# Power_Board_Testing_Interface_Board_manu.net
KiCad netlist of a schematic drawn in EAGLE
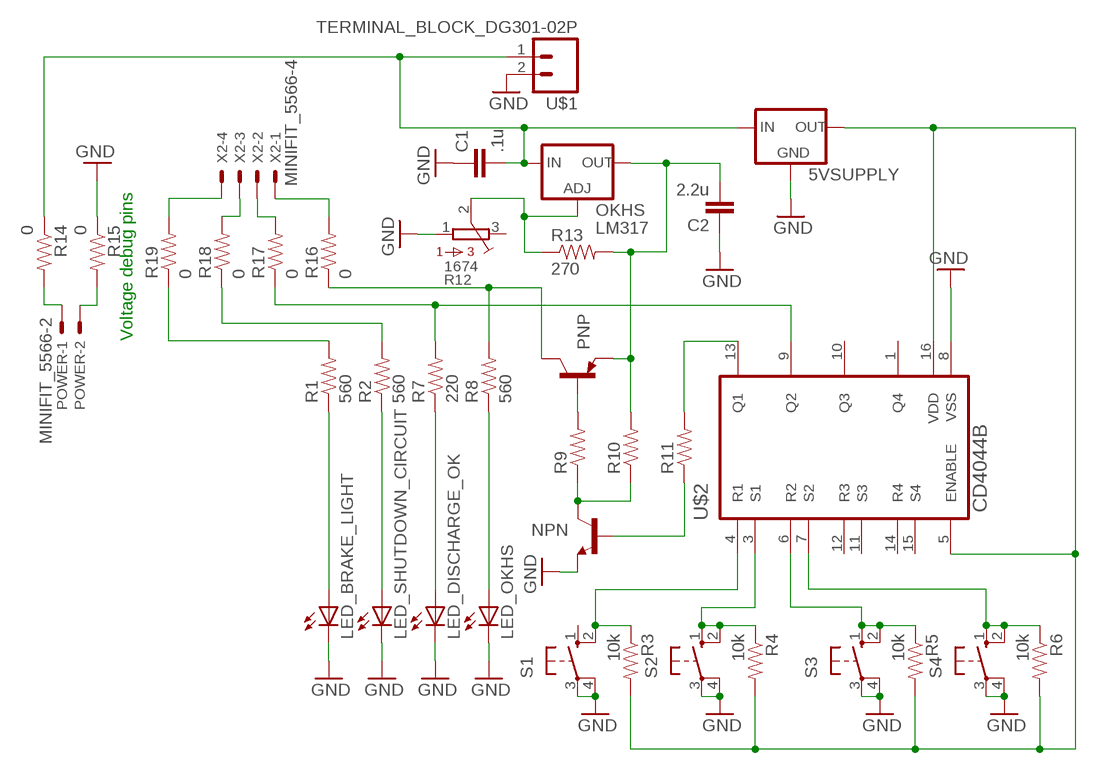
[diagram p0: schematic, sheet 1]

(export (version "E")
  (design (tool "Eeschema 10.0.6"))
  (components
    (comp (ref "5VSUPPLY")
      (value "5V_REGULATOR_L7805SWITCHING")
      (footprint "eagle-import:TO-220")
      (libsource (lib "eagle-import") (part "5V_REGULATOR_L7805SWITCHING"))
    )
    (comp (ref "C1")
      (value ".1u")
      (footprint "eagle-import:CAP-PTH-SMALLEZ")
      (libsource (lib "eagle-import") (part "CAPEZ"))
    )
    (comp (ref "C2")
      (value "2.2u")
      (footprint "eagle-import:CAP-PTH-5MM")
      (libsource (lib "eagle-import") (part "CAPPTH1"))
    )
    (comp (ref "LED_BRAKE_LIGHT")
      (value "LED-5MM")
      (footprint "eagle-import:LED-5MM")
      (libsource (lib "eagle-import") (part "LED-5MM"))
    )
    (comp (ref "LED_DISCHARGE_OK")
      (value "LED-5MM")
      (footprint "eagle-import:LED-5MM")
      (libsource (lib "eagle-import") (part "LED-5MM"))
    )
    (comp (ref "LED_OKHS")
      (value "LED-5MM")
      (footprint "eagle-import:LED-5MM")
      (libsource (lib "eagle-import") (part "LED-5MM"))
    )
    (comp (ref "LED_SHUTDOWN_CIRCUIT")
      (value "LED-5MM")
      (footprint "eagle-import:LED-5MM")
      (libsource (lib "eagle-import") (part "LED-5MM"))
    )
    (comp (ref "NPN")
      (value "BJT_NPNTIP120")
      (footprint "eagle-import:TO-220")
      (libsource (lib "eagle-import") (part "BJT_NPNTIP120"))
    )
    (comp (ref "OKHS")
      (value "LM317")
      (footprint "eagle-import:TO-220")
      (libsource (lib "eagle-import") (part "LM317"))
    )
    (comp (ref "PNP")
      (value "BJT_PNP")
      (footprint "eagle-import:TO-220")
      (libsource (lib "eagle-import") (part "BJT_PNP"))
    )
    (comp (ref "POWER")
      (value "MINIFIT_5566-2")
      (footprint "eagle-import:MINIFIT_5566-2")
      (libsource (lib "eagle-import") (part "MINIFIT_5566-2"))
    )
    (comp (ref "R1")
      (value "560")
      (footprint "eagle-import:AXIAL-0.3EZ")
      (libsource (lib "eagle-import") (part "RESISTOREZ"))
    )
    (comp (ref "R2")
      (value "560")
      (footprint "eagle-import:AXIAL-0.3EZ")
      (libsource (lib "eagle-import") (part "RESISTOREZ"))
    )
    (comp (ref "R3")
      (value "10k")
      (footprint "eagle-import:AXIAL-0.3EZ")
      (libsource (lib "eagle-import") (part "RESISTOREZ"))
    )
    (comp (ref "R4")
      (value "10k")
      (footprint "eagle-import:AXIAL-0.3EZ")
      (libsource (lib "eagle-import") (part "RESISTOREZ"))
    )
    (comp (ref "R5")
      (value "10k")
      (footprint "eagle-import:AXIAL-0.3EZ")
      (libsource (lib "eagle-import") (part "RESISTOREZ"))
    )
    (comp (ref "R6")
      (value "10k")
      (footprint "eagle-import:AXIAL-0.3EZ")
      (libsource (lib "eagle-import") (part "RESISTOREZ"))
    )
    (comp (ref "R7")
      (value "220")
      (footprint "eagle-import:AXIAL-0.3EZ")
      (libsource (lib "eagle-import") (part "RESISTOREZ"))
    )
    (comp (ref "R8")
      (value "560")
      (footprint "eagle-import:AXIAL-0.3EZ")
      (libsource (lib "eagle-import") (part "RESISTOREZ"))
    )
    (comp (ref "R9")
      (value "RESISTOREZ")
      (footprint "eagle-import:AXIAL-0.3EZ")
      (libsource (lib "eagle-import") (part "RESISTOREZ"))
    )
    (comp (ref "R10")
      (value "RESISTOREZ")
      (footprint "eagle-import:AXIAL-0.3EZ")
      (libsource (lib "eagle-import") (part "RESISTOREZ"))
    )
    (comp (ref "R11")
      (value "RESISTOREZ")
      (footprint "eagle-import:AXIAL-0.3EZ")
      (libsource (lib "eagle-import") (part "RESISTOREZ"))
    )
    (comp (ref "R12")
      (value "1674")
      (footprint "eagle-import:TRIMPOT_3296")
      (libsource (lib "eagle-import") (part "TRIMPOT_3296C"))
    )
    (comp (ref "R13")
      (value "270")
      (footprint "eagle-import:AXIAL-0.3EZ")
      (libsource (lib "eagle-import") (part "RESISTOREZ"))
    )
    (comp (ref "R14")
      (value "0")
      (footprint "eagle-import:AXIAL-0.3EZ")
      (libsource (lib "eagle-import") (part "RESISTOREZ"))
    )
    (comp (ref "R15")
      (value "0")
      (footprint "eagle-import:AXIAL-0.3EZ")
      (libsource (lib "eagle-import") (part "RESISTOREZ"))
    )
    (comp (ref "R16")
      (value "0")
      (footprint "eagle-import:AXIAL-0.3EZ")
      (libsource (lib "eagle-import") (part "RESISTOREZ"))
    )
    (comp (ref "R17")
      (value "0")
      (footprint "eagle-import:AXIAL-0.3EZ")
      (libsource (lib "eagle-import") (part "RESISTOREZ"))
    )
    (comp (ref "R18")
      (value "0")
      (footprint "eagle-import:AXIAL-0.3EZ")
      (libsource (lib "eagle-import") (part "RESISTOREZ"))
    )
    (comp (ref "R19")
      (value "0")
      (footprint "eagle-import:AXIAL-0.3EZ")
      (libsource (lib "eagle-import") (part "RESISTOREZ"))
    )
    (comp (ref "S1")
      (value "BTN_10-XX")
      (footprint "eagle-import:B3F-10XX")
      (fields (field (name "MPN") "B3F-1000"))
      (libsource (lib "eagle-import") (part "BTN_10-XX"))
    )
    (comp (ref "S2")
      (value "BTN_10-XX")
      (footprint "eagle-import:B3F-10XX")
      (fields (field (name "MPN") "B3F-1000"))
      (libsource (lib "eagle-import") (part "BTN_10-XX"))
    )
    (comp (ref "S3")
      (value "BTN_10-XX")
      (footprint "eagle-import:B3F-10XX")
      (fields (field (name "MPN") "B3F-1000"))
      (libsource (lib "eagle-import") (part "BTN_10-XX"))
    )
    (comp (ref "S4")
      (value "BTN_10-XX")
      (footprint "eagle-import:B3F-10XX")
      (fields (field (name "MPN") "B3F-1000"))
      (libsource (lib "eagle-import") (part "BTN_10-XX"))
    )
    (comp (ref "U$1")
      (value "TERMINAL_BLOCK_DG301-02P")
      (footprint "eagle-import:DG301-02P")
      (libsource (lib "eagle-import") (part "TERMINAL_BLOCK_DG301-02P"))
    )
    (comp (ref "U$2")
      (value "CD4044B")
      (footprint "eagle-import:DIL16")
      (libsource (lib "eagle-import") (part "CD4044B"))
    )
    (comp (ref "X2")
      (value "MINIFIT_5566-4")
      (footprint "eagle-import:MINIFIT_5566-4")
      (libsource (lib "eagle-import") (part "MINIFIT_5566-4"))
    )
  )
  (nets
    (net (code "1") (name "GND") (class "Default")
      (node (ref "5VSUPPLY") (pin "2") (pinfunction "GND_2") (pintype "input"))
      (node (ref "C1") (pin "1") (pinfunction "1_1") (pintype "passive"))
      (node (ref "C2") (pin "1") (pinfunction "1_1") (pintype "passive"))
      (node (ref "LED_BRAKE_LIGHT") (pin "K") (pinfunction "C_K") (pintype "passive"))
      (node (ref "LED_DISCHARGE_OK") (pin "K") (pinfunction "C_K") (pintype "passive"))
      (node (ref "LED_OKHS") (pin "K") (pinfunction "C_K") (pintype "passive"))
      (node (ref "LED_SHUTDOWN_CIRCUIT") (pin "K") (pinfunction "C_K") (pintype "passive"))
      (node (ref "NPN") (pin "3") (pinfunction "EMITTER_3") (pintype "passive"))
      (node (ref "R12") (pin "1") (pinfunction "1_1") (pintype "passive"))
      (node (ref "R15") (pin "P$1") (pinfunction "1_P$1") (pintype "passive"))
      (node (ref "S1") (pin "3") (pinfunction "P_3") (pintype "passive"))
      (node (ref "S1") (pin "4") (pinfunction "P1_4") (pintype "passive"))
      (node (ref "S2") (pin "3") (pinfunction "P_3") (pintype "passive"))
      (node (ref "S2") (pin "4") (pinfunction "P1_4") (pintype "passive"))
      (node (ref "S3") (pin "3") (pinfunction "P_3") (pintype "passive"))
      (node (ref "S3") (pin "4") (pinfunction "P1_4") (pintype "passive"))
      (node (ref "S4") (pin "3") (pinfunction "P_3") (pintype "passive"))
      (node (ref "S4") (pin "4") (pinfunction "P1_4") (pintype "passive"))
      (node (ref "U$1") (pin "2") (pinfunction "2_2") (pintype "passive"))
      (node (ref "U$2") (pin "8") (pinfunction "VSS_8") (pintype "output"))
    )
    (net (code "2") (name "Net-(5VSUPPLY-IN)") (class "Default")
      (node (ref "5VSUPPLY") (pin "1") (pinfunction "IN_1") (pintype "input"))
      (node (ref "C1") (pin "2") (pinfunction "2_2") (pintype "passive"))
      (node (ref "OKHS") (pin "3") (pinfunction "IN_3") (pintype "input"))
      (node (ref "R14") (pin "P$1") (pinfunction "1_P$1") (pintype "passive"))
      (node (ref "U$1") (pin "1") (pinfunction "1_1") (pintype "passive"))
    )
    (net (code "3") (name "Net-(5VSUPPLY-OUT)") (class "Default")
      (node (ref "5VSUPPLY") (pin "3") (pinfunction "OUT_3") (pintype "output"))
      (node (ref "R3") (pin "P$2") (pinfunction "2_P$2") (pintype "passive"))
      (node (ref "R4") (pin "P$2") (pinfunction "2_P$2") (pintype "passive"))
      (node (ref "R5") (pin "P$2") (pinfunction "2_P$2") (pintype "passive"))
      (node (ref "R6") (pin "P$2") (pinfunction "2_P$2") (pintype "passive"))
      (node (ref "U$2") (pin "16") (pinfunction "VDD_16") (pintype "input"))
      (node (ref "U$2") (pin "5") (pinfunction "ENABLE_5") (pintype "input"))
    )
    (net (code "4") (name "Net-(NPN-BASE)") (class "Default")
      (node (ref "NPN") (pin "1") (pinfunction "BASE_1") (pintype "passive"))
      (node (ref "R11") (pin "P$1") (pinfunction "1_P$1") (pintype "passive"))
    )
    (net (code "5") (name "Net-(NPN-COLLECTOR)") (class "Default")
      (node (ref "NPN") (pin "2") (pinfunction "COLLECTOR_2") (pintype "passive"))
      (node (ref "R10") (pin "P$1") (pinfunction "1_P$1") (pintype "passive"))
      (node (ref "R9") (pin "P$1") (pinfunction "1_P$1") (pintype "passive"))
    )
    (net (code "6") (name "Net-(OKHS-ADJ)") (class "Default")
      (node (ref "OKHS") (pin "1") (pinfunction "ADJ_1") (pintype "input"))
      (node (ref "R12") (pin "2") (pinfunction "2_2") (pintype "passive"))
      (node (ref "R13") (pin "P$1") (pinfunction "1_P$1") (pintype "passive"))
    )
    (net (code "7") (name "Net-(OKHS-OUT)") (class "Default")
      (node (ref "C2") (pin "2") (pinfunction "2_2") (pintype "passive"))
      (node (ref "OKHS") (pin "2") (pinfunction "OUT_2") (pintype "output"))
      (node (ref "PNP") (pin "3") (pinfunction "E_3") (pintype "passive"))
      (node (ref "R10") (pin "P$2") (pinfunction "2_P$2") (pintype "passive"))
      (node (ref "R13") (pin "P$2") (pinfunction "2_P$2") (pintype "passive"))
    )
    (net (code "8") (name "Net-(PNP-B)") (class "Default")
      (node (ref "PNP") (pin "1") (pinfunction "B_1") (pintype "passive"))
      (node (ref "R9") (pin "P$2") (pinfunction "2_P$2") (pintype "passive"))
    )
    (net (code "9") (name "Net-(PNP-C)") (class "Default")
      (node (ref "PNP") (pin "2") (pinfunction "C_2") (pintype "passive"))
      (node (ref "R16") (pin "P$1") (pinfunction "1_P$1") (pintype "passive"))
      (node (ref "R8") (pin "P$2") (pinfunction "2_P$2") (pintype "passive"))
    )
    (net (code "10") (name "Net-(POWERA-S)") (class "Default")
      (node (ref "POWER") (pin "1") (pinfunction "S_1") (pintype "passive"))
      (node (ref "R14") (pin "P$2") (pinfunction "2_P$2") (pintype "passive"))
    )
    (net (code "11") (name "Net-(POWERB-S)") (class "Default")
      (node (ref "POWER") (pin "2") (pinfunction "S_2") (pintype "passive"))
      (node (ref "R15") (pin "P$2") (pinfunction "2_P$2") (pintype "passive"))
    )
    (net (code "12") (name "Net-(R1-1)") (class "Default")
      (node (ref "LED_BRAKE_LIGHT") (pin "A") (pinfunction "A_A") (pintype "passive"))
      (node (ref "R1") (pin "P$1") (pinfunction "1_P$1") (pintype "passive"))
    )
    (net (code "13") (name "Net-(R1-2)") (class "Default")
      (node (ref "R1") (pin "P$2") (pinfunction "2_P$2") (pintype "passive"))
      (node (ref "R19") (pin "P$1") (pinfunction "1_P$1") (pintype "passive"))
    )
    (net (code "14") (name "Net-(R2-1)") (class "Default")
      (node (ref "LED_SHUTDOWN_CIRCUIT") (pin "A") (pinfunction "A_A") (pintype "passive"))
      (node (ref "R2") (pin "P$1") (pinfunction "1_P$1") (pintype "passive"))
    )
    (net (code "15") (name "Net-(R3-1)") (class "Default")
      (node (ref "R3") (pin "P$1") (pinfunction "1_P$1") (pintype "passive"))
      (node (ref "S1") (pin "2") (pinfunction "S1_2") (pintype "passive"))
      (node (ref "U$2") (pin "4") (pinfunction "R1_4") (pintype "input"))
    )
    (net (code "16") (name "Net-(R4-1)") (class "Default")
      (node (ref "R4") (pin "P$1") (pinfunction "1_P$1") (pintype "passive"))
      (node (ref "S2") (pin "1") (pinfunction "S_1") (pintype "passive"))
      (node (ref "S2") (pin "2") (pinfunction "S1_2") (pintype "passive"))
      (node (ref "U$2") (pin "3") (pinfunction "S1_3") (pintype "input"))
    )
    (net (code "17") (name "Net-(R5-1)") (class "Default")
      (node (ref "R5") (pin "P$1") (pinfunction "1_P$1") (pintype "passive"))
      (node (ref "S3") (pin "1") (pinfunction "S_1") (pintype "passive"))
      (node (ref "S3") (pin "2") (pinfunction "S1_2") (pintype "passive"))
      (node (ref "U$2") (pin "6") (pinfunction "R2_6") (pintype "input"))
    )
    (net (code "18") (name "Net-(R6-1)") (class "Default")
      (node (ref "R6") (pin "P$1") (pinfunction "1_P$1") (pintype "passive"))
      (node (ref "S4") (pin "1") (pinfunction "S_1") (pintype "passive"))
      (node (ref "S4") (pin "2") (pinfunction "S1_2") (pintype "passive"))
      (node (ref "U$2") (pin "7") (pinfunction "S2_7") (pintype "input"))
    )
    (net (code "19") (name "Net-(R7-1)") (class "Default")
      (node (ref "LED_DISCHARGE_OK") (pin "A") (pinfunction "A_A") (pintype "passive"))
      (node (ref "R7") (pin "P$1") (pinfunction "1_P$1") (pintype "passive"))
    )
    (net (code "20") (name "Net-(R8-1)") (class "Default")
      (node (ref "LED_OKHS") (pin "A") (pinfunction "A_A") (pintype "passive"))
      (node (ref "R8") (pin "P$1") (pinfunction "1_P$1") (pintype "passive"))
    )
    (net (code "21") (name "Net-(R11-2)") (class "Default")
      (node (ref "R11") (pin "P$2") (pinfunction "2_P$2") (pintype "passive"))
      (node (ref "U$2") (pin "13") (pinfunction "Q1_13") (pintype "output"))
    )
    (net (code "22") (name "Net-(R16-2)") (class "Default")
      (node (ref "R16") (pin "P$2") (pinfunction "2_P$2") (pintype "passive"))
      (node (ref "X2") (pin "1") (pinfunction "S_1") (pintype "passive"))
    )
    (net (code "23") (name "Net-(R17-1)") (class "Default")
      (node (ref "R17") (pin "P$1") (pinfunction "1_P$1") (pintype "passive"))
      (node (ref "R7") (pin "P$2") (pinfunction "2_P$2") (pintype "passive"))
      (node (ref "U$2") (pin "9") (pinfunction "Q2_9") (pintype "output"))
    )
    (net (code "24") (name "Net-(R17-2)") (class "Default")
      (node (ref "R17") (pin "P$2") (pinfunction "2_P$2") (pintype "passive"))
      (node (ref "X2") (pin "2") (pinfunction "S_2") (pintype "passive"))
    )
    (net (code "25") (name "Net-(R18-1)") (class "Default")
      (node (ref "R18") (pin "P$1") (pinfunction "1_P$1") (pintype "passive"))
      (node (ref "R2") (pin "P$2") (pinfunction "2_P$2") (pintype "passive"))
    )
    (net (code "26") (name "Net-(R18-2)") (class "Default")
      (node (ref "R18") (pin "P$2") (pinfunction "2_P$2") (pintype "passive"))
      (node (ref "X2") (pin "3") (pinfunction "S_3") (pintype "passive"))
    )
    (net (code "27") (name "Net-(R19-2)") (class "Default")
      (node (ref "R19") (pin "P$2") (pinfunction "2_P$2") (pintype "passive"))
      (node (ref "X2") (pin "4") (pinfunction "S_4") (pintype "passive"))
    )
    (net (code "28") (name "unconnected-(R12-Pad3)") (class "Default")
      (node (ref "R12") (pin "3") (pinfunction "3_3") (pintype "passive"))
    )
    (net (code "29") (name "unconnected-(S1-S-Pad1)") (class "Default")
      (node (ref "S1") (pin "1") (pinfunction "S_1") (pintype "passive"))
    )
    (net (code "30") (name "unconnected-(U$2-Q3-Pad10)") (class "Default")
      (node (ref "U$2") (pin "10") (pinfunction "Q3_10") (pintype "output"))
    )
    (net (code "31") (name "unconnected-(U$2-Q4-Pad1)") (class "Default")
      (node (ref "U$2") (pin "1") (pinfunction "Q4_1") (pintype "output"))
    )
    (net (code "32") (name "unconnected-(U$2-R3-Pad12)") (class "Default")
      (node (ref "U$2") (pin "12") (pinfunction "R3_12") (pintype "input"))
    )
    (net (code "33") (name "unconnected-(U$2-R4-Pad14)") (class "Default")
      (node (ref "U$2") (pin "14") (pinfunction "R4_14") (pintype "input"))
    )
    (net (code "34") (name "unconnected-(U$2-S3-Pad11)") (class "Default")
      (node (ref "U$2") (pin "11") (pinfunction "S3_11") (pintype "input"))
    )
    (net (code "35") (name "unconnected-(U$2-S4-Pad15)") (class "Default")
      (node (ref "U$2") (pin "15") (pinfunction "S4_15") (pintype "input"))
    )
  )
)
